# LR2021.net
KiCad netlist of a schematic drawn in Altium Designer
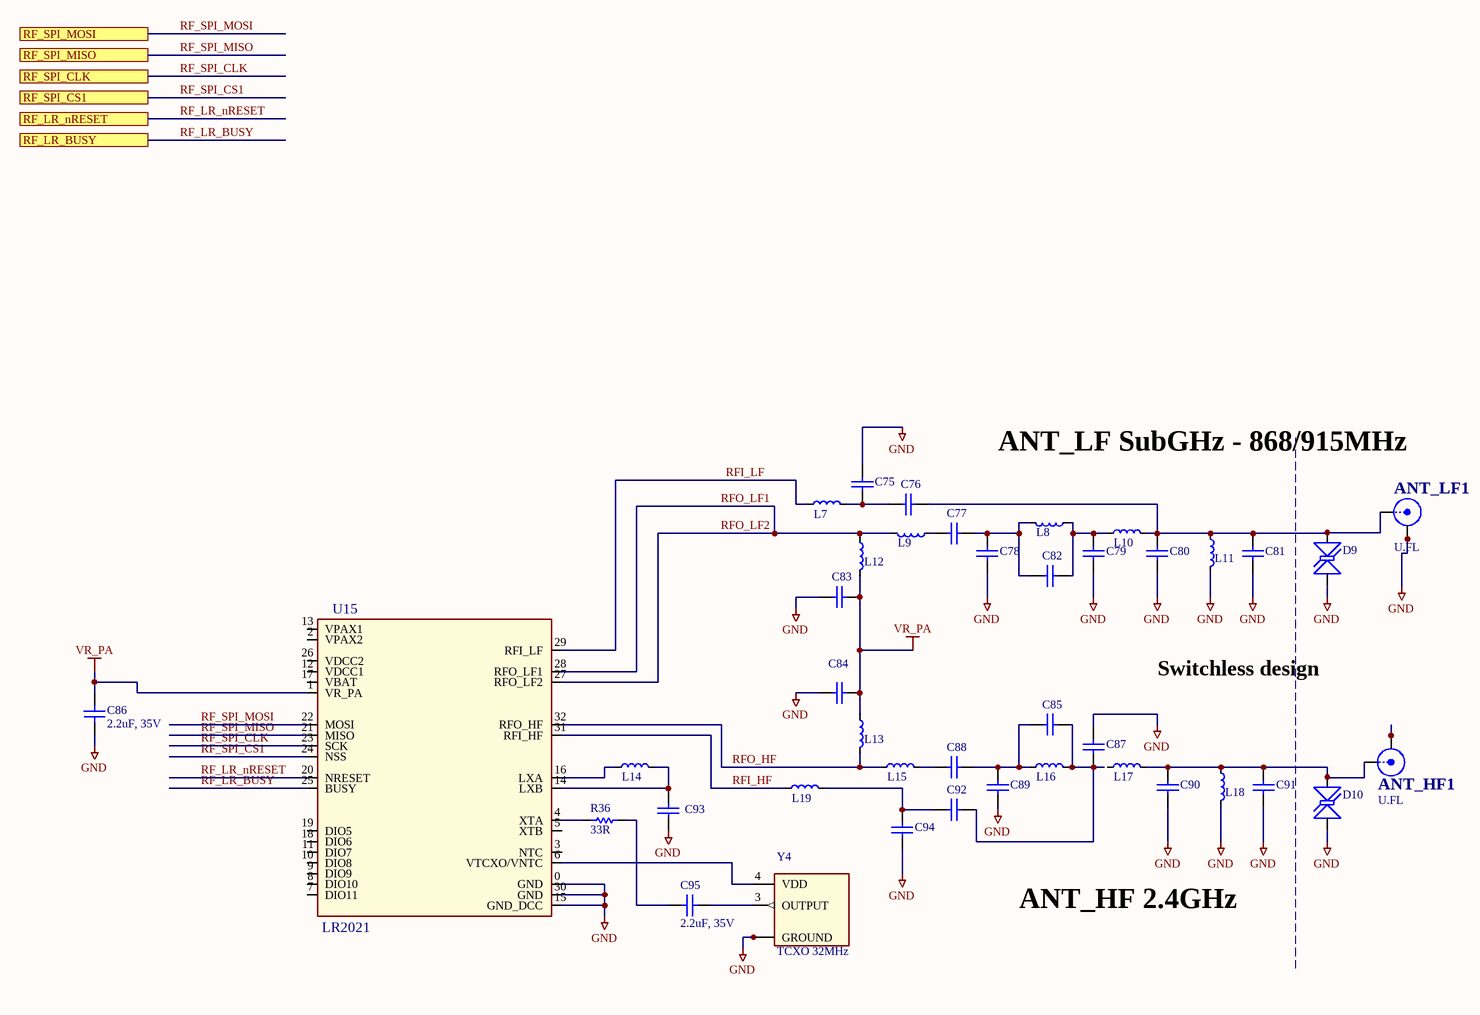
[diagram p0: LR2021.SchDoc]

(export (version "E")
  (design (tool "Eeschema 10.0.6"))
  (components
    (comp (ref "ANT_HF1")
      (value "U.FL")
      (footprint "U.FL-R-SMT Hirose_2337019-1")
      (description "U.FL Hirose RF Connector")
      (libsource (lib "LR2021_Wio_868-915_e769v01a") (part "U.FL"))
    )
    (comp (ref "ANT_LF1")
      (value "U.FL")
      (footprint "U.FL-R-SMT Hirose_2337019-1")
      (description "U.FL Hirose RF Connector")
      (libsource (lib "LR2021_Wio_868-915_e769v01a") (part "U.FL"))
    )
    (comp (ref "C75")
      (value "Cap")
      (footprint "c_201_smd")
      (description "Capacitor SMD")
      (fields (field (name "PUBLISHER") "Altium Limited"))
      (libsource (lib "LR2021_Wio_868-915_e769v01a") (part "Cap"))
    )
    (comp (ref "C76")
      (value "Cap")
      (footprint "c_201_smd")
      (description "Capacitor SMD")
      (fields (field (name "PUBLISHER") "Altium Limited"))
      (libsource (lib "LR2021_Wio_868-915_e769v01a") (part "Cap"))
    )
    (comp (ref "C77")
      (value "Cap")
      (footprint "c_201_smd")
      (description "Capacitor SMD")
      (fields (field (name "PUBLISHER") "Altium Limited"))
      (libsource (lib "LR2021_Wio_868-915_e769v01a") (part "Cap"))
    )
    (comp (ref "C78")
      (value "Cap")
      (footprint "c_201_smd")
      (description "Capacitor SMD")
      (fields (field (name "PUBLISHER") "Altium Limited"))
      (libsource (lib "LR2021_Wio_868-915_e769v01a") (part "Cap"))
    )
    (comp (ref "C79")
      (value "Cap")
      (footprint "c_201_smd")
      (description "Capacitor SMD")
      (fields (field (name "PUBLISHER") "Altium Limited"))
      (libsource (lib "LR2021_Wio_868-915_e769v01a") (part "Cap"))
    )
    (comp (ref "C80")
      (value "Cap")
      (footprint "c_201_smd")
      (description "Capacitor SMD")
      (fields (field (name "PUBLISHER") "Altium Limited"))
      (libsource (lib "LR2021_Wio_868-915_e769v01a") (part "Cap"))
    )
    (comp (ref "C81")
      (value "Cap")
      (footprint "c_201_smd")
      (description "Capacitor SMD")
      (fields (field (name "PUBLISHER") "Altium Limited"))
      (libsource (lib "LR2021_Wio_868-915_e769v01a") (part "Cap"))
    )
    (comp (ref "C82")
      (value "Cap")
      (footprint "c_201_smd")
      (description "Capacitor SMD")
      (fields (field (name "PUBLISHER") "Altium Limited"))
      (libsource (lib "LR2021_Wio_868-915_e769v01a") (part "Cap"))
    )
    (comp (ref "C83")
      (value "Cap")
      (footprint "c_201_smd")
      (description "Capacitor SMD")
      (fields (field (name "PUBLISHER") "Altium Limited"))
      (libsource (lib "LR2021_Wio_868-915_e769v01a") (part "Cap"))
    )
    (comp (ref "C84")
      (value "Cap")
      (footprint "c_201_smd")
      (description "Capacitor SMD")
      (fields (field (name "PUBLISHER") "Altium Limited"))
      (libsource (lib "LR2021_Wio_868-915_e769v01a") (part "Cap"))
    )
    (comp (ref "C85")
      (value "Cap")
      (footprint "c_201_smd")
      (description "Capacitor SMD")
      (fields (field (name "PUBLISHER") "Altium Limited"))
      (libsource (lib "LR2021_Wio_868-915_e769v01a") (part "Cap"))
    )
    (comp (ref "C86")
      (value "2.2uF, 35V")
      (footprint "0402 resistor")
      (description "2.2uF, 35V, 10%, 0402")
      (libsource (lib "Revolve NTNU") (part "CAP"))
    )
    (comp (ref "C87")
      (value "Cap")
      (footprint "c_201_smd")
      (description "Capacitor SMD")
      (fields (field (name "PUBLISHER") "Altium Limited"))
      (libsource (lib "LR2021_Wio_868-915_e769v01a") (part "Cap"))
    )
    (comp (ref "C88")
      (value "Cap")
      (footprint "c_201_smd")
      (description "Capacitor SMD")
      (fields (field (name "PUBLISHER") "Altium Limited"))
      (libsource (lib "LR2021_Wio_868-915_e769v01a") (part "Cap"))
    )
    (comp (ref "C89")
      (value "Cap")
      (footprint "c_201_smd")
      (description "Capacitor SMD")
      (fields (field (name "PUBLISHER") "Altium Limited"))
      (libsource (lib "LR2021_Wio_868-915_e769v01a") (part "Cap"))
    )
    (comp (ref "C90")
      (value "Cap")
      (footprint "c_201_smd")
      (description "Capacitor SMD")
      (fields (field (name "PUBLISHER") "Altium Limited"))
      (libsource (lib "LR2021_Wio_868-915_e769v01a") (part "Cap"))
    )
    (comp (ref "C91")
      (value "Cap")
      (footprint "c_201_smd")
      (description "Capacitor SMD")
      (fields (field (name "PUBLISHER") "Altium Limited"))
      (libsource (lib "LR2021_Wio_868-915_e769v01a") (part "Cap"))
    )
    (comp (ref "C92")
      (value "Cap")
      (footprint "c_201_smd")
      (description "Capacitor SMD")
      (fields (field (name "PUBLISHER") "Altium Limited"))
      (libsource (lib "LR2021_Wio_868-915_e769v01a") (part "Cap"))
    )
    (comp (ref "C93")
      (value "Cap")
      (footprint "c_201_smd")
      (description "Capacitor SMD")
      (fields (field (name "PUBLISHER") "Altium Limited"))
      (libsource (lib "LR2021_Wio_868-915_e769v01a") (part "Cap"))
    )
    (comp (ref "C94")
      (value "Cap")
      (footprint "c_201_smd")
      (description "Capacitor SMD")
      (fields (field (name "PUBLISHER") "Altium Limited"))
      (libsource (lib "LR2021_Wio_868-915_e769v01a") (part "Cap"))
    )
    (comp (ref "C95")
      (value "2.2uF, 35V")
      (footprint "0402 resistor")
      (description "2.2uF, 35V, 10%, 0402")
      (libsource (lib "Revolve NTNU") (part "CAP"))
    )
    (comp (ref "D9")
      (value "TVS Diode")
      (footprint "SLP0603P2X3F")
      (description "Ultra Low Capacitance 1-line ESD Protection")
      (libsource (lib "LR2021_Wio_868-915_e769v01a") (part "TVS Diode"))
    )
    (comp (ref "D10")
      (value "TVS Diode")
      (footprint "SLP0603P2X3F")
      (description "Ultra Low Capacitance 1-line ESD Protection")
      (libsource (lib "LR2021_Wio_868-915_e769v01a") (part "TVS Diode"))
    )
    (comp (ref "L7")
      (value "Inductor symbol")
      (footprint "LQW_201_smd")
      (description "Inductor")
      (fields (field (name "PUBLISHER") "Altium Limited"))
      (libsource (lib "") (part "Inductor_1"))
    )
    (comp (ref "L8")
      (value "Inductor symbol")
      (footprint "LQW_201_smd")
      (description "Inductor")
      (fields (field (name "PUBLISHER") "Altium Limited"))
      (libsource (lib "LR2021_Wio_868-915_e769v01a") (part "Inductor"))
    )
    (comp (ref "L9")
      (value "Inductor symbol")
      (footprint "LQW_201_smd")
      (description "Inductor")
      (fields (field (name "PUBLISHER") "Altium Limited"))
      (libsource (lib "LR2021_Wio_868-915_e769v01a") (part "Inductor"))
    )
    (comp (ref "L10")
      (value "Inductor symbol")
      (footprint "LQW_201_smd")
      (description "Inductor")
      (fields (field (name "PUBLISHER") "Altium Limited"))
      (libsource (lib "") (part "Inductor_1"))
    )
    (comp (ref "L11")
      (value "Inductor symbol")
      (footprint "LQW_201_smd")
      (description "Inductor")
      (fields (field (name "PUBLISHER") "Altium Limited"))
      (libsource (lib "") (part "Inductor_1"))
    )
    (comp (ref "L12")
      (value "Inductor symbol")
      (footprint "lqw_402_smd")
      (description "Inductor")
      (fields (field (name "PUBLISHER") "Altium Limited"))
      (libsource (lib "LR2021_Wio_868-915_e769v01a") (part "Inductor"))
    )
    (comp (ref "L13")
      (value "Inductor symbol")
      (footprint "LQW_201_smd")
      (description "Inductor")
      (fields (field (name "PUBLISHER") "Altium Limited"))
      (libsource (lib "") (part "Inductor_1"))
    )
    (comp (ref "L14")
      (value "Inductor symbol")
      (footprint "LQM18P_603_INDUCTOR_SMD")
      (description "Inductor for DC-DC")
      (fields (field (name "PUBLISHER") "Altium Limited"))
      (libsource (lib "LR2021_Wio_868-915_e769v01a") (part "Inductor_DC-DC"))
    )
    (comp (ref "L15")
      (value "Inductor symbol")
      (footprint "LQW_201_smd")
      (description "Inductor")
      (fields (field (name "PUBLISHER") "Altium Limited"))
      (libsource (lib "") (part "Inductor_1"))
    )
    (comp (ref "L16")
      (value "Inductor symbol")
      (footprint "LQW_201_smd")
      (description "Inductor")
      (fields (field (name "PUBLISHER") "Altium Limited"))
      (libsource (lib "") (part "Inductor_1"))
    )
    (comp (ref "L17")
      (value "Inductor symbol")
      (footprint "LQW_201_smd")
      (description "Inductor")
      (fields (field (name "PUBLISHER") "Altium Limited"))
      (libsource (lib "") (part "Inductor_1"))
    )
    (comp (ref "L18")
      (value "Inductor symbol")
      (footprint "LQW_201_smd")
      (description "Inductor")
      (fields (field (name "PUBLISHER") "Altium Limited"))
      (libsource (lib "") (part "Inductor_1"))
    )
    (comp (ref "L19")
      (value "Inductor symbol")
      (footprint "LQW_201_smd")
      (description "Inductor")
      (fields (field (name "PUBLISHER") "Altium Limited"))
      (libsource (lib "LR2021_Wio_868-915_e769v01a") (part "Inductor"))
    )
    (comp (ref "R36")
      (value "33R")
      (footprint "0603 Resistor")
      (description "33R, 1%, 1/10W, 0603")
      (fields (field (name "TOLERANCE") "1%") (field (name "MANUFACTURER") "Panasonic"))
      (libsource (lib "Revolve NTNU") (part "Resistor"))
    )
    (comp (ref "U15")
      (value "LR2021")
      (footprint "qfn32l_5x5mm")
      (description "LR2021 - Low Power Integrated Low Power Multi protocol Transceiver")
      (libsource (lib "Handheld") (part "LR2021"))
    )
    (comp (ref "Y4")
      (value "TCXO 32MHz")
      (footprint "XTAL_ECS-400-10-37B2-CKM-TR")
      (description "32 MHz TCXO Clipped Sine Wave Oscillator 1.7V ~ 3.465V - 4-SMD, No Lead")
      (fields (field (name "MF") "ECS Inc.") (field (name "MP") "ECS-TXO-20CSMV-320-EY-TR"))
      (libsource (lib "Handheld") (part "ECSTXO20CSMV320EYTR"))
    )
  )
  (nets
    (net (code "1") (name "/RFI_HF") (class "Default")
      (node (ref "L19") (pin "2") (pinfunction "2_2") (pintype "passive"))
      (node (ref "U15") (pin "31") (pinfunction "RFI_HF_31") (pintype "passive"))
    )
    (net (code "2") (name "/RFI_LF") (class "Default")
      (node (ref "L7") (pin "1") (pinfunction "1_1") (pintype "passive"))
      (node (ref "U15") (pin "29") (pinfunction "RFI_LF_29") (pintype "passive"))
    )
    (net (code "3") (name "/RFO_HF") (class "Default")
      (node (ref "L13") (pin "2") (pinfunction "2_2") (pintype "passive"))
      (node (ref "L15") (pin "1") (pinfunction "1_1") (pintype "passive"))
      (node (ref "U15") (pin "32") (pinfunction "RFO_HF_32") (pintype "passive"))
    )
    (net (code "4") (name "/RFO_LF1") (class "Default")
      (node (ref "L12") (pin "2") (pinfunction "2_2") (pintype "passive"))
      (node (ref "L9") (pin "1") (pinfunction "1_1") (pintype "passive"))
      (node (ref "U15") (pin "27") (pinfunction "RFO_LF2_27") (pintype "passive"))
      (node (ref "U15") (pin "28") (pinfunction "RFO_LF1_28") (pintype "passive"))
    )
    (net (code "5") (name "/RF_LR_BUSY") (class "Default")
      (node (ref "U15") (pin "25") (pinfunction "BUSY_25") (pintype "passive"))
    )
    (net (code "6") (name "/RF_LR_nRESET") (class "Default")
      (node (ref "U15") (pin "20") (pinfunction "NRESET_20") (pintype "passive"))
    )
    (net (code "7") (name "/RF_SPI_CLK") (class "Default")
      (node (ref "U15") (pin "23") (pinfunction "SCK_23") (pintype "passive"))
    )
    (net (code "8") (name "/RF_SPI_CS1") (class "Default")
      (node (ref "U15") (pin "24") (pinfunction "NSS_24") (pintype "passive"))
    )
    (net (code "9") (name "/RF_SPI_MISO") (class "Default")
      (node (ref "U15") (pin "21") (pinfunction "MISO_21") (pintype "passive"))
    )
    (net (code "10") (name "/RF_SPI_MOSI") (class "Default")
      (node (ref "U15") (pin "22") (pinfunction "MOSI_22") (pintype "passive"))
    )
    (net (code "11") (name "GND") (class "Default")
      (node (ref "ANT_LF1") (pin "2") (pinfunction "GND_2") (pintype "passive"))
      (node (ref "ANT_LF1") (pin "3") (pinfunction "GND_3") (pintype "passive"))
      (node (ref "C75") (pin "1") (pinfunction "1_1") (pintype "passive"))
      (node (ref "C78") (pin "1") (pinfunction "1_1") (pintype "passive"))
      (node (ref "C79") (pin "1") (pinfunction "1_1") (pintype "passive"))
      (node (ref "C80") (pin "1") (pinfunction "1_1") (pintype "passive"))
      (node (ref "C81") (pin "2") (pinfunction "2_2") (pintype "passive"))
      (node (ref "C83") (pin "1") (pinfunction "1_1") (pintype "passive"))
      (node (ref "C84") (pin "1") (pinfunction "1_1") (pintype "passive"))
      (node (ref "C86") (pin "2") (pinfunction "2_2") (pintype "passive"))
      (node (ref "C87") (pin "1") (pinfunction "1_1") (pintype "passive"))
      (node (ref "C89") (pin "1") (pinfunction "1_1") (pintype "passive"))
      (node (ref "C90") (pin "1") (pinfunction "1_1") (pintype "passive"))
      (node (ref "C91") (pin "1") (pinfunction "1_1") (pintype "passive"))
      (node (ref "C93") (pin "1") (pinfunction "1_1") (pintype "passive"))
      (node (ref "C94") (pin "1") (pinfunction "1_1") (pintype "passive"))
      (node (ref "D10") (pin "1") (pinfunction "A_1") (pintype "passive"))
      (node (ref "D9") (pin "1") (pinfunction "A_1") (pintype "passive"))
      (node (ref "L11") (pin "2") (pinfunction "2_2") (pintype "passive"))
      (node (ref "L18") (pin "2") (pinfunction "2_2") (pintype "passive"))
      (node (ref "U15") (pin "0") (pinfunction "GND_0") (pintype "passive"))
      (node (ref "U15") (pin "15") (pinfunction "GND_DCC_15") (pintype "passive"))
      (node (ref "U15") (pin "30") (pinfunction "GND_30") (pintype "passive"))
      (node (ref "Y4") (pin "1") (pinfunction "GROUND_1") (pintype "power_in"))
      (node (ref "Y4") (pin "2") (pinfunction "GROUND_2") (pintype "power_in"))
    )
    (net (code "12") (name "Net-(ANT_HF1-GND-Pad2)") (class "Default")
      (node (ref "ANT_HF1") (pin "2") (pinfunction "GND_2") (pintype "passive"))
      (node (ref "ANT_HF1") (pin "3") (pinfunction "GND_3") (pintype "passive"))
    )
    (net (code "13") (name "Net-(ANT_HF1-Signal)") (class "Default")
      (node (ref "ANT_HF1") (pin "1") (pinfunction "Signal_1") (pintype "passive"))
      (node (ref "C90") (pin "2") (pinfunction "2_2") (pintype "passive"))
      (node (ref "C91") (pin "2") (pinfunction "2_2") (pintype "passive"))
      (node (ref "D10") (pin "2") (pinfunction "K_2") (pintype "passive"))
      (node (ref "L17") (pin "2") (pinfunction "2_2") (pintype "passive"))
      (node (ref "L18") (pin "1") (pinfunction "1_1") (pintype "passive"))
    )
    (net (code "14") (name "Net-(ANT_LF1-Signal)") (class "Default")
      (node (ref "ANT_LF1") (pin "1") (pinfunction "Signal_1") (pintype "passive"))
      (node (ref "C76") (pin "2") (pinfunction "2_2") (pintype "passive"))
      (node (ref "C80") (pin "2") (pinfunction "2_2") (pintype "passive"))
      (node (ref "C81") (pin "1") (pinfunction "1_1") (pintype "passive"))
      (node (ref "D9") (pin "2") (pinfunction "K_2") (pintype "passive"))
      (node (ref "L10") (pin "2") (pinfunction "2_2") (pintype "passive"))
      (node (ref "L11") (pin "1") (pinfunction "1_1") (pintype "passive"))
    )
    (net (code "15") (name "Net-(C75-Pad2)") (class "Default")
      (node (ref "C75") (pin "2") (pinfunction "2_2") (pintype "passive"))
      (node (ref "C76") (pin "1") (pinfunction "1_1") (pintype "passive"))
      (node (ref "L7") (pin "2") (pinfunction "2_2") (pintype "passive"))
    )
    (net (code "16") (name "Net-(C77-Pad1)") (class "Default")
      (node (ref "C77") (pin "1") (pinfunction "1_1") (pintype "passive"))
      (node (ref "L9") (pin "2") (pinfunction "2_2") (pintype "passive"))
    )
    (net (code "17") (name "Net-(C77-Pad2)") (class "Default")
      (node (ref "C77") (pin "2") (pinfunction "2_2") (pintype "passive"))
      (node (ref "C78") (pin "2") (pinfunction "2_2") (pintype "passive"))
      (node (ref "C82") (pin "1") (pinfunction "1_1") (pintype "passive"))
      (node (ref "L8") (pin "1") (pinfunction "1_1") (pintype "passive"))
    )
    (net (code "18") (name "Net-(C79-Pad2)") (class "Default")
      (node (ref "C79") (pin "2") (pinfunction "2_2") (pintype "passive"))
      (node (ref "C82") (pin "2") (pinfunction "2_2") (pintype "passive"))
      (node (ref "L10") (pin "1") (pinfunction "1_1") (pintype "passive"))
      (node (ref "L8") (pin "2") (pinfunction "2_2") (pintype "passive"))
    )
    (net (code "19") (name "Net-(C85-Pad1)") (class "Default")
      (node (ref "C85") (pin "1") (pinfunction "1_1") (pintype "passive"))
      (node (ref "C88") (pin "2") (pinfunction "2_2") (pintype "passive"))
      (node (ref "C89") (pin "2") (pinfunction "2_2") (pintype "passive"))
      (node (ref "L16") (pin "1") (pinfunction "1_1") (pintype "passive"))
    )
    (net (code "20") (name "Net-(C85-Pad2)") (class "Default")
      (node (ref "C85") (pin "2") (pinfunction "2_2") (pintype "passive"))
      (node (ref "C87") (pin "2") (pinfunction "2_2") (pintype "passive"))
      (node (ref "C92") (pin "2") (pinfunction "2_2") (pintype "passive"))
      (node (ref "L16") (pin "2") (pinfunction "2_2") (pintype "passive"))
    )
    (net (code "21") (name "Net-(C88-Pad1)") (class "Default")
      (node (ref "C88") (pin "1") (pinfunction "1_1") (pintype "passive"))
      (node (ref "L15") (pin "2") (pinfunction "2_2") (pintype "passive"))
    )
    (net (code "22") (name "Net-(C92-Pad1)") (class "Default")
      (node (ref "C92") (pin "1") (pinfunction "1_1") (pintype "passive"))
      (node (ref "C94") (pin "2") (pinfunction "2_2") (pintype "passive"))
      (node (ref "L19") (pin "1") (pinfunction "1_1") (pintype "passive"))
    )
    (net (code "23") (name "Net-(C95-Pad2)") (class "Default")
      (node (ref "C95") (pin "2") (pinfunction "2_2") (pintype "passive"))
      (node (ref "R36") (pin "2") (pinfunction "2_2") (pintype "passive"))
    )
    (net (code "24") (name "Net-(U15-LXA)") (class "Default")
      (node (ref "L14") (pin "1") (pinfunction "1_1") (pintype "passive"))
      (node (ref "U15") (pin "16") (pinfunction "LXA_16") (pintype "passive"))
    )
    (net (code "25") (name "Net-(U15-LXB)") (class "Default")
      (node (ref "C93") (pin "2") (pinfunction "2_2") (pintype "passive"))
      (node (ref "L14") (pin "2") (pinfunction "2_2") (pintype "passive"))
      (node (ref "U15") (pin "14") (pinfunction "LXB_14") (pintype "passive"))
    )
    (net (code "26") (name "Net-(U15-VTCXO{slash}VNTC)") (class "Default")
      (node (ref "U15") (pin "6") (pinfunction "VTCXO/VNTC_6") (pintype "passive"))
      (node (ref "Y4") (pin "4") (pinfunction "VDD_4") (pintype "power_in"))
    )
    (net (code "27") (name "Net-(U15-XTA)") (class "Default")
      (node (ref "R36") (pin "1") (pinfunction "1_1") (pintype "passive"))
      (node (ref "U15") (pin "4") (pinfunction "XTA_4") (pintype "passive"))
    )
    (net (code "28") (name "Net-(Y4-OUTPUT)") (class "Default")
      (node (ref "C95") (pin "1") (pinfunction "1_1") (pintype "passive"))
      (node (ref "Y4") (pin "3") (pinfunction "OUTPUT_3") (pintype "output"))
    )
    (net (code "29") (name "VR_PA") (class "Default")
      (node (ref "C83") (pin "2") (pinfunction "2_2") (pintype "passive"))
      (node (ref "C84") (pin "2") (pinfunction "2_2") (pintype "passive"))
      (node (ref "C86") (pin "1") (pinfunction "1_1") (pintype "passive"))
      (node (ref "L12") (pin "1") (pinfunction "1_1") (pintype "passive"))
      (node (ref "L13") (pin "1") (pinfunction "1_1") (pintype "passive"))
      (node (ref "U15") (pin "1") (pinfunction "VR_PA_1") (pintype "passive"))
    )
    (net (code "30") (name "unconnected-(L17-Pad1)") (class "Default")
      (node (ref "L17") (pin "1") (pinfunction "1_1") (pintype "passive"))
    )
    (net (code "31") (name "unconnected-(U15-DIO5-Pad19)") (class "Default")
      (node (ref "U15") (pin "19") (pinfunction "DIO5_19") (pintype "passive"))
    )
    (net (code "32") (name "unconnected-(U15-DIO6-Pad18)") (class "Default")
      (node (ref "U15") (pin "18") (pinfunction "DIO6_18") (pintype "passive"))
    )
    (net (code "33") (name "unconnected-(U15-DIO7-Pad11)") (class "Default")
      (node (ref "U15") (pin "11") (pinfunction "DIO7_11") (pintype "passive"))
    )
    (net (code "34") (name "unconnected-(U15-DIO8-Pad10)") (class "Default")
      (node (ref "U15") (pin "10") (pinfunction "DIO8_10") (pintype "passive"))
    )
    (net (code "35") (name "unconnected-(U15-DIO9-Pad9)") (class "Default")
      (node (ref "U15") (pin "9") (pinfunction "DIO9_9") (pintype "passive"))
    )
    (net (code "36") (name "unconnected-(U15-DIO10-Pad8)") (class "Default")
      (node (ref "U15") (pin "8") (pinfunction "DIO10_8") (pintype "passive"))
    )
    (net (code "37") (name "unconnected-(U15-DIO11-Pad7)") (class "Default")
      (node (ref "U15") (pin "7") (pinfunction "DIO11_7") (pintype "passive"))
    )
    (net (code "38") (name "unconnected-(U15-NTC-Pad3)") (class "Default")
      (node (ref "U15") (pin "3") (pinfunction "NTC_3") (pintype "passive"))
    )
    (net (code "39") (name "unconnected-(U15-VBAT-Pad17)") (class "Default")
      (node (ref "U15") (pin "17") (pinfunction "VBAT_17") (pintype "passive"))
    )
    (net (code "40") (name "unconnected-(U15-VDCC1-Pad12)") (class "Default")
      (node (ref "U15") (pin "12") (pinfunction "VDCC1_12") (pintype "passive"))
    )
    (net (code "41") (name "unconnected-(U15-VDCC2-Pad26)") (class "Default")
      (node (ref "U15") (pin "26") (pinfunction "VDCC2_26") (pintype "passive"))
    )
    (net (code "42") (name "unconnected-(U15-VPAX1-Pad13)") (class "Default")
      (node (ref "U15") (pin "13") (pinfunction "VPAX1_13") (pintype "passive"))
    )
    (net (code "43") (name "unconnected-(U15-VPAX2-Pad2)") (class "Default")
      (node (ref "U15") (pin "2") (pinfunction "VPAX2_2") (pintype "passive"))
    )
    (net (code "44") (name "unconnected-(U15-XTB-Pad5)") (class "Default")
      (node (ref "U15") (pin "5") (pinfunction "XTB_5") (pintype "passive"))
    )
  )
)
